# testShield.net
KiCad netlist of a schematic drawn in EAGLE
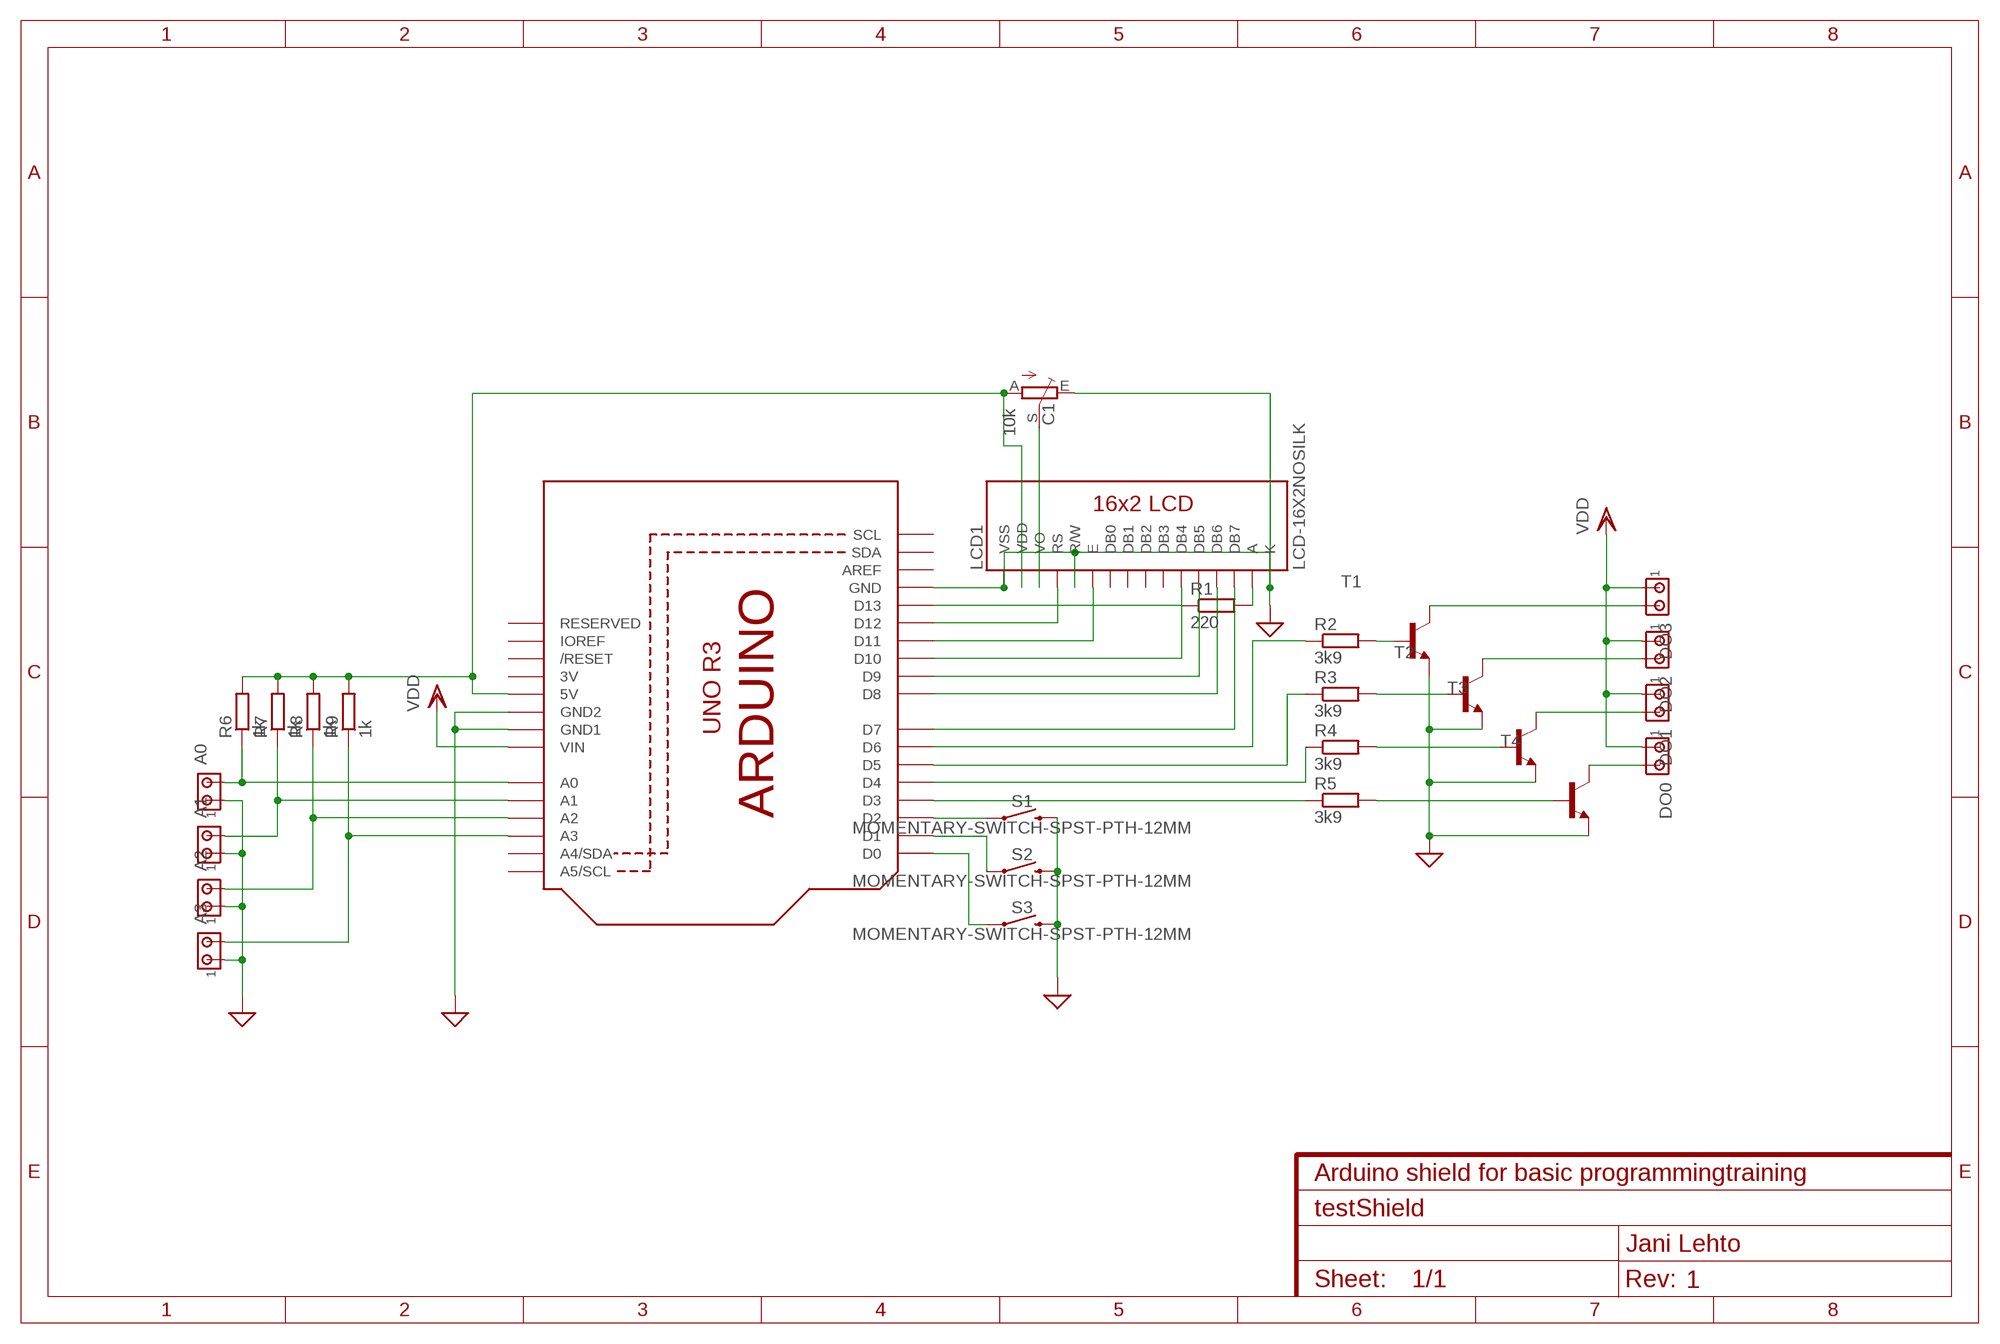
[diagram p0: schematic, sheet 1]

(export (version "E")
  (design (tool "Eeschema 10.0.6"))
  (components
    (comp (ref "A0")
      (value "MTA02-156")
      (footprint "eagle-import:1X2MTA")
      (libsource (lib "eagle-import") (part "MTA02-156"))
    )
    (comp (ref "A1")
      (value "MTA02-156")
      (footprint "eagle-import:1X2MTA")
      (libsource (lib "eagle-import") (part "MTA02-156"))
    )
    (comp (ref "A2")
      (value "MTA02-156")
      (footprint "eagle-import:1X2MTA")
      (libsource (lib "eagle-import") (part "MTA02-156"))
    )
    (comp (ref "A3")
      (value "MTA02-156")
      (footprint "eagle-import:1X2MTA")
      (libsource (lib "eagle-import") (part "MTA02-156"))
    )
    (comp (ref "C1")
      (value "10k")
      (footprint "eagle-import:CA9V")
      (libsource (lib "eagle-import") (part "TRIM_EU-CA9V"))
    )
    (comp (ref "DO0")
      (value "MTA02-156")
      (footprint "eagle-import:1X2MTA")
      (libsource (lib "eagle-import") (part "MTA02-156"))
    )
    (comp (ref "DO1")
      (value "MTA02-156")
      (footprint "eagle-import:1X2MTA")
      (libsource (lib "eagle-import") (part "MTA02-156"))
    )
    (comp (ref "DO2")
      (value "MTA02-156")
      (footprint "eagle-import:1X2MTA")
      (libsource (lib "eagle-import") (part "MTA02-156"))
    )
    (comp (ref "DO3")
      (value "MTA02-156")
      (footprint "eagle-import:1X2MTA")
      (libsource (lib "eagle-import") (part "MTA02-156"))
    )
    (comp (ref "LCD1")
      (value "LCD-16X2NOSILK")
      (footprint "eagle-import:LCD-16X2_NOSILK")
      (libsource (lib "eagle-import") (part "LCD-16X2NOSILK"))
    )
    (comp (ref "R1")
      (value "220")
      (footprint "eagle-import:0617_22")
      (libsource (lib "eagle-import") (part "R-EU_0617/22"))
    )
    (comp (ref "R2")
      (value "3k9")
      (footprint "eagle-import:0207_12")
      (libsource (lib "eagle-import") (part "R-EU_0207/12"))
    )
    (comp (ref "R3")
      (value "3k9")
      (footprint "eagle-import:0207_12")
      (libsource (lib "eagle-import") (part "R-EU_0207/12"))
    )
    (comp (ref "R4")
      (value "3k9")
      (footprint "eagle-import:0207_12")
      (libsource (lib "eagle-import") (part "R-EU_0207/12"))
    )
    (comp (ref "R5")
      (value "3k9")
      (footprint "eagle-import:0207_12")
      (libsource (lib "eagle-import") (part "R-EU_0207/12"))
    )
    (comp (ref "R6")
      (value "1k")
      (footprint "eagle-import:0207_12")
      (libsource (lib "eagle-import") (part "R-EU_0207/12"))
    )
    (comp (ref "R7")
      (value "1k")
      (footprint "eagle-import:0207_12")
      (libsource (lib "eagle-import") (part "R-EU_0207/12"))
    )
    (comp (ref "R8")
      (value "1k")
      (footprint "eagle-import:0207_12")
      (libsource (lib "eagle-import") (part "R-EU_0207/12"))
    )
    (comp (ref "R9")
      (value "1k")
      (footprint "eagle-import:0207_12")
      (libsource (lib "eagle-import") (part "R-EU_0207/12"))
    )
    (comp (ref "S1")
      (value "MOMENTARY-SWITCH-SPST-PTH-12MM")
      (footprint "eagle-import:TACTILE_SWITCH_PTH_12MM")
      (libsource (lib "eagle-import") (part "MOMENTARY-SWITCH-SPST-PTH-12MM"))
    )
    (comp (ref "S2")
      (value "MOMENTARY-SWITCH-SPST-PTH-12MM")
      (footprint "eagle-import:TACTILE_SWITCH_PTH_12MM")
      (libsource (lib "eagle-import") (part "MOMENTARY-SWITCH-SPST-PTH-12MM"))
    )
    (comp (ref "S3")
      (value "MOMENTARY-SWITCH-SPST-PTH-12MM")
      (footprint "eagle-import:TACTILE_SWITCH_PTH_12MM")
      (libsource (lib "eagle-import") (part "MOMENTARY-SWITCH-SPST-PTH-12MM"))
    )
    (comp (ref "T1")
      (value "BC547-NPN-TO92-CBE")
      (footprint "eagle-import:TO92-CBE")
      (libsource (lib "eagle-import") (part "-NPN-TO92-CBEBC547"))
    )
    (comp (ref "T2")
      (value "BC547-NPN-TO92-CBE")
      (footprint "eagle-import:TO92-CBE")
      (libsource (lib "eagle-import") (part "-NPN-TO92-CBEBC547"))
    )
    (comp (ref "T3")
      (value "BC547-NPN-TO92-CBE")
      (footprint "eagle-import:TO92-CBE")
      (libsource (lib "eagle-import") (part "-NPN-TO92-CBEBC547"))
    )
    (comp (ref "T4")
      (value "BC547-NPN-TO92-CBE")
      (footprint "eagle-import:TO92-CBE")
      (libsource (lib "eagle-import") (part "-NPN-TO92-CBEBC547"))
    )
    (comp (ref "U1")
      (value "ARDUINOR3-BPLACE")
      (footprint "eagle-import:ARDUINOR3-BPLACE")
      (libsource (lib "eagle-import") (part "ARDUINOR3-BPLACE"))
    )
  )
  (nets
    (net (code "1") (name "/3V") (class "Default")
      (node (ref "U1") (pin "3V") (pinfunction "3V_3V") (pintype "power_in"))
    )
    (net (code "2") (name "Net-(A0-Pad2)") (class "Default")
      (node (ref "A0") (pin "2") (pinfunction "2_2") (pintype "passive"))
      (node (ref "R6") (pin "1") (pinfunction "1_1") (pintype "passive"))
      (node (ref "U1") (pin "A0") (pinfunction "A0_A0") (pintype "bidirectional"))
    )
    (net (code "3") (name "Net-(A1-Pad2)") (class "Default")
      (node (ref "A1") (pin "2") (pinfunction "2_2") (pintype "passive"))
      (node (ref "R7") (pin "1") (pinfunction "1_1") (pintype "passive"))
      (node (ref "U1") (pin "A1") (pinfunction "A1_A1") (pintype "bidirectional"))
    )
    (net (code "4") (name "Net-(A2-Pad2)") (class "Default")
      (node (ref "A2") (pin "2") (pinfunction "2_2") (pintype "passive"))
      (node (ref "R8") (pin "1") (pinfunction "1_1") (pintype "passive"))
      (node (ref "U1") (pin "A2") (pinfunction "A2_A2") (pintype "bidirectional"))
    )
    (net (code "5") (name "Net-(A3-Pad2)") (class "Default")
      (node (ref "A3") (pin "2") (pinfunction "2_2") (pintype "passive"))
      (node (ref "R9") (pin "1") (pinfunction "1_1") (pintype "passive"))
      (node (ref "U1") (pin "A3") (pinfunction "A3_A3") (pintype "bidirectional"))
    )
    (net (code "6") (name "Net-(DO0-Pad2)") (class "Default")
      (node (ref "DO0") (pin "2") (pinfunction "2_2") (pintype "passive"))
      (node (ref "T4") (pin "C") (pinfunction "C_C") (pintype "passive"))
    )
    (net (code "7") (name "Net-(DO1-Pad2)") (class "Default")
      (node (ref "DO1") (pin "2") (pinfunction "2_2") (pintype "passive"))
      (node (ref "T3") (pin "C") (pinfunction "C_C") (pintype "passive"))
    )
    (net (code "8") (name "Net-(DO2-Pad2)") (class "Default")
      (node (ref "DO2") (pin "2") (pinfunction "2_2") (pintype "passive"))
      (node (ref "T2") (pin "C") (pinfunction "C_C") (pintype "passive"))
    )
    (net (code "9") (name "Net-(DO3-Pad2)") (class "Default")
      (node (ref "DO3") (pin "2") (pinfunction "2_2") (pintype "passive"))
      (node (ref "T1") (pin "C") (pinfunction "C_C") (pintype "passive"))
    )
    (net (code "10") (name "Net-(LCD1-A)") (class "Default")
      (node (ref "LCD1") (pin "15") (pinfunction "A_15") (pintype "power_in"))
      (node (ref "R1") (pin "2") (pinfunction "2_2") (pintype "passive"))
    )
    (net (code "11") (name "Net-(LCD1-DB4)") (class "Default")
      (node (ref "LCD1") (pin "11") (pinfunction "DB4_11") (pintype "bidirectional"))
      (node (ref "U1") (pin "D10") (pinfunction "D10_D10") (pintype "bidirectional"))
    )
    (net (code "12") (name "Net-(LCD1-DB5)") (class "Default")
      (node (ref "LCD1") (pin "12") (pinfunction "DB5_12") (pintype "bidirectional"))
      (node (ref "U1") (pin "D9") (pinfunction "D9_D9") (pintype "bidirectional"))
    )
    (net (code "13") (name "Net-(LCD1-DB6)") (class "Default")
      (node (ref "LCD1") (pin "13") (pinfunction "DB6_13") (pintype "bidirectional"))
      (node (ref "U1") (pin "D8") (pinfunction "D8_D8") (pintype "bidirectional"))
    )
    (net (code "14") (name "Net-(LCD1-DB7)") (class "Default")
      (node (ref "LCD1") (pin "14") (pinfunction "DB7_14") (pintype "bidirectional"))
      (node (ref "U1") (pin "D7") (pinfunction "D7_D7") (pintype "bidirectional"))
    )
    (net (code "15") (name "Net-(LCD1-E)") (class "Default")
      (node (ref "LCD1") (pin "6") (pinfunction "E_6") (pintype "input"))
      (node (ref "U1") (pin "D11") (pinfunction "D11_D11") (pintype "bidirectional"))
    )
    (net (code "16") (name "Net-(LCD1-RS)") (class "Default")
      (node (ref "LCD1") (pin "4") (pinfunction "RS_4") (pintype "input"))
      (node (ref "U1") (pin "D12") (pinfunction "D12_D12") (pintype "bidirectional"))
    )
    (net (code "17") (name "Net-(LCD1-VDD)") (class "Default")
      (node (ref "C1") (pin "A") (pinfunction "A_A") (pintype "passive"))
      (node (ref "LCD1") (pin "2") (pinfunction "VDD_2") (pintype "power_in"))
      (node (ref "R6") (pin "2") (pinfunction "2_2") (pintype "passive"))
      (node (ref "R7") (pin "2") (pinfunction "2_2") (pintype "passive"))
      (node (ref "R8") (pin "2") (pinfunction "2_2") (pintype "passive"))
      (node (ref "R9") (pin "2") (pinfunction "2_2") (pintype "passive"))
      (node (ref "U1") (pin "5V") (pinfunction "5V_5V") (pintype "power_in"))
    )
    (net (code "18") (name "Net-(LCD1-VO)") (class "Default")
      (node (ref "C1") (pin "S") (pinfunction "S_S") (pintype "passive"))
      (node (ref "LCD1") (pin "3") (pinfunction "VO_3") (pintype "bidirectional"))
    )
    (net (code "19") (name "Net-(R1-Pad1)") (class "Default")
      (node (ref "R1") (pin "1") (pinfunction "1_1") (pintype "passive"))
      (node (ref "U1") (pin "D13") (pinfunction "D13_D13") (pintype "bidirectional"))
    )
    (net (code "20") (name "Net-(R2-Pad1)") (class "Default")
      (node (ref "R2") (pin "1") (pinfunction "1_1") (pintype "passive"))
      (node (ref "U1") (pin "D6") (pinfunction "D6_D6") (pintype "bidirectional"))
    )
    (net (code "21") (name "Net-(R2-Pad2)") (class "Default")
      (node (ref "R2") (pin "2") (pinfunction "2_2") (pintype "passive"))
      (node (ref "T1") (pin "B") (pinfunction "B_B") (pintype "passive"))
    )
    (net (code "22") (name "Net-(R3-Pad1)") (class "Default")
      (node (ref "R3") (pin "1") (pinfunction "1_1") (pintype "passive"))
      (node (ref "U1") (pin "D5") (pinfunction "D5_D5") (pintype "bidirectional"))
    )
    (net (code "23") (name "Net-(R3-Pad2)") (class "Default")
      (node (ref "R3") (pin "2") (pinfunction "2_2") (pintype "passive"))
      (node (ref "T2") (pin "B") (pinfunction "B_B") (pintype "passive"))
    )
    (net (code "24") (name "Net-(R4-Pad1)") (class "Default")
      (node (ref "R4") (pin "1") (pinfunction "1_1") (pintype "passive"))
      (node (ref "U1") (pin "D4") (pinfunction "D4_D4") (pintype "bidirectional"))
    )
    (net (code "25") (name "Net-(R4-Pad2)") (class "Default")
      (node (ref "R4") (pin "2") (pinfunction "2_2") (pintype "passive"))
      (node (ref "T3") (pin "B") (pinfunction "B_B") (pintype "passive"))
    )
    (net (code "26") (name "Net-(R5-Pad1)") (class "Default")
      (node (ref "R5") (pin "1") (pinfunction "1_1") (pintype "passive"))
      (node (ref "U1") (pin "D3") (pinfunction "D3_D3") (pintype "bidirectional"))
    )
    (net (code "27") (name "Net-(R5-Pad2)") (class "Default")
      (node (ref "R5") (pin "2") (pinfunction "2_2") (pintype "passive"))
      (node (ref "T4") (pin "B") (pinfunction "B_B") (pintype "passive"))
    )
    (net (code "28") (name "Net-(S1-Pad1)") (class "Default")
      (node (ref "S1") (pin "1") (pinfunction "1_1") (pintype "passive"))
      (node (ref "U1") (pin "D2") (pinfunction "D2_D2") (pintype "bidirectional"))
    )
    (net (code "29") (name "Net-(S2-Pad1)") (class "Default")
      (node (ref "S2") (pin "1") (pinfunction "1_1") (pintype "passive"))
      (node (ref "U1") (pin "D1") (pinfunction "D1_D1") (pintype "bidirectional"))
    )
    (net (code "30") (name "Net-(S3-Pad1)") (class "Default")
      (node (ref "S3") (pin "1") (pinfunction "1_1") (pintype "passive"))
      (node (ref "U1") (pin "D0") (pinfunction "D0_D0") (pintype "bidirectional"))
    )
    (net (code "31") (name "SUP") (class "Default")
      (node (ref "A0") (pin "1") (pinfunction "1_1") (pintype "passive"))
      (node (ref "A1") (pin "1") (pinfunction "1_1") (pintype "passive"))
      (node (ref "A2") (pin "1") (pinfunction "1_1") (pintype "passive"))
      (node (ref "A3") (pin "1") (pinfunction "1_1") (pintype "passive"))
      (node (ref "C1") (pin "E") (pinfunction "E_E") (pintype "passive"))
      (node (ref "LCD1") (pin "1") (pinfunction "VSS_1") (pintype "power_in"))
      (node (ref "LCD1") (pin "16") (pinfunction "K_16") (pintype "power_in"))
      (node (ref "LCD1") (pin "5") (pinfunction "R/W_5") (pintype "input"))
      (node (ref "S1") (pin "3") (pinfunction "2_3") (pintype "passive"))
      (node (ref "S2") (pin "3") (pinfunction "2_3") (pintype "passive"))
      (node (ref "S3") (pin "3") (pinfunction "2_3") (pintype "passive"))
      (node (ref "T1") (pin "E") (pinfunction "E_E") (pintype "passive"))
      (node (ref "T2") (pin "E") (pinfunction "E_E") (pintype "passive"))
      (node (ref "T3") (pin "E") (pinfunction "E_E") (pintype "passive"))
      (node (ref "T4") (pin "E") (pinfunction "E_E") (pintype "passive"))
      (node (ref "U1") (pin "GND") (pinfunction "GND_GND") (pintype "power_in"))
      (node (ref "U1") (pin "GND1") (pinfunction "GND1_GND1") (pintype "power_in"))
      (node (ref "U1") (pin "GND2") (pinfunction "GND2_GND2") (pintype "power_in"))
    )
    (net (code "32") (name "VDD") (class "Default")
      (node (ref "DO0") (pin "1") (pinfunction "1_1") (pintype "passive"))
      (node (ref "DO1") (pin "1") (pinfunction "1_1") (pintype "passive"))
      (node (ref "DO2") (pin "1") (pinfunction "1_1") (pintype "passive"))
      (node (ref "DO3") (pin "1") (pinfunction "1_1") (pintype "passive"))
      (node (ref "U1") (pin "VIN") (pinfunction "VIN_VIN") (pintype "power_in"))
    )
    (net (code "33") (name "unconnected-(LCD1-DB0-Pad7)") (class "Default")
      (node (ref "LCD1") (pin "7") (pinfunction "DB0_7") (pintype "bidirectional"))
    )
    (net (code "34") (name "unconnected-(LCD1-DB1-Pad8)") (class "Default")
      (node (ref "LCD1") (pin "8") (pinfunction "DB1_8") (pintype "bidirectional"))
    )
    (net (code "35") (name "unconnected-(LCD1-DB2-Pad9)") (class "Default")
      (node (ref "LCD1") (pin "9") (pinfunction "DB2_9") (pintype "bidirectional"))
    )
    (net (code "36") (name "unconnected-(LCD1-DB3-Pad10)") (class "Default")
      (node (ref "LCD1") (pin "10") (pinfunction "DB3_10") (pintype "bidirectional"))
    )
    (net (code "37") (name "unconnected-(U1-A4{slash}SDA-PadA4)") (class "Default")
      (node (ref "U1") (pin "A4") (pinfunction "A4/SDA_A4") (pintype "bidirectional"))
    )
    (net (code "38") (name "unconnected-(U1-A5{slash}SCL-PadA5)") (class "Default")
      (node (ref "U1") (pin "A5") (pinfunction "A5/SCL_A5") (pintype "bidirectional"))
    )
    (net (code "39") (name "unconnected-(U1-PadAREF)") (class "Default")
      (node (ref "U1") (pin "AREF") (pinfunction "AREF_AREF") (pintype "bidirectional"))
    )
    (net (code "40") (name "unconnected-(U1-PadIOREF)") (class "Default")
      (node (ref "U1") (pin "IOREF") (pinfunction "IOREF_IOREF") (pintype "output"))
    )
    (net (code "41") (name "unconnected-(U1-PadRESERVED)") (class "Default")
      (node (ref "U1") (pin "RESERVED") (pinfunction "RESERVED_RESERVED") (pintype "no_connect"))
    )
    (net (code "42") (name "unconnected-(U1-PadSCL)") (class "Default")
      (node (ref "U1") (pin "SCL") (pinfunction "SCL_SCL") (pintype "bidirectional"))
    )
    (net (code "43") (name "unconnected-(U1-PadSDA)") (class "Default")
      (node (ref "U1") (pin "SDA") (pinfunction "SDA_SDA") (pintype "bidirectional"))
    )
    (net (code "44") (name "unconnected-(U1-{slash}RESET-PadRESET)") (class "Default")
      (node (ref "U1") (pin "RESET") (pinfunction "/RESET_RESET") (pintype "bidirectional"))
    )
  )
)
